# Stepper_Motor_Driver.net
KiCad netlist of a schematic drawn in Altium Designer
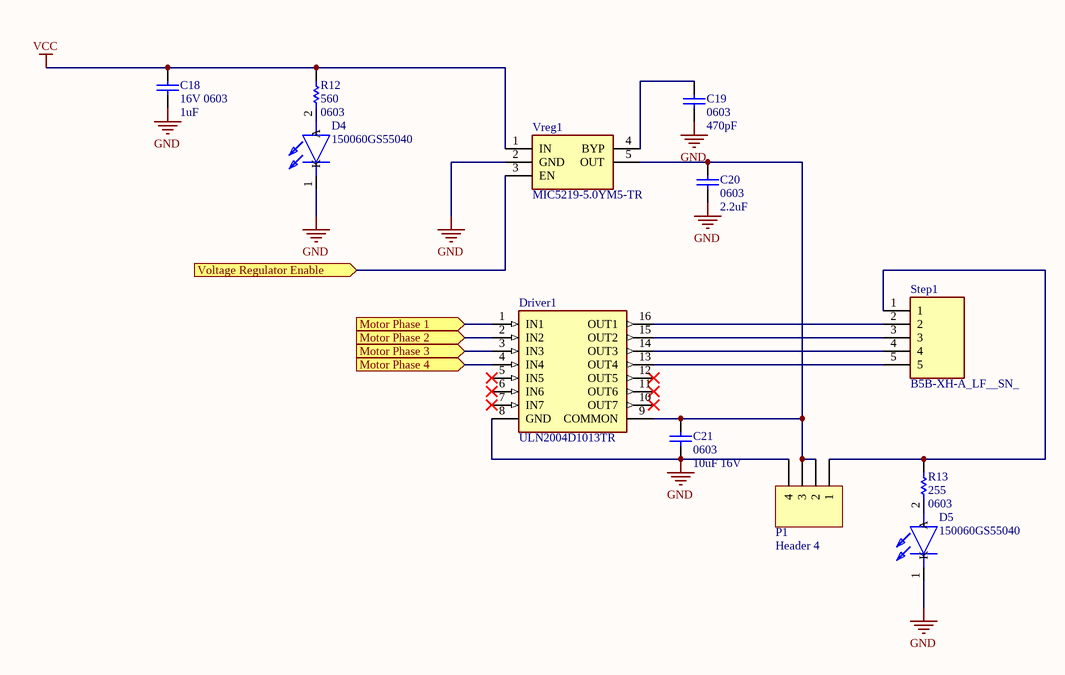
[diagram p0: Stepper Motor Driver.SchDoc]

(export (version "E")
  (design (tool "Eeschema 10.0.6"))
  (components
    (comp (ref "C18")
      (value "16V 0603")
      (footprint "SMD-0603C")
      (description "Capacitor")
      (fields (field (name "ALTIUM_VALUE") "1uF") (field (name "PUBLISHER") "Altium Limited"))
      (libsource (lib "Miscellaneous Devices") (part "Cap"))
    )
    (comp (ref "C19")
      (value "0603")
      (footprint "SMD-0603C")
      (description "Capacitor")
      (fields (field (name "ALTIUM_VALUE") "470pF") (field (name "PUBLISHER") "Altium Limited"))
      (libsource (lib "Miscellaneous Devices") (part "Cap"))
    )
    (comp (ref "C20")
      (value "0603")
      (footprint "SMD-0603C")
      (description "Capacitor")
      (fields (field (name "ALTIUM_VALUE") "2.2uF") (field (name "PUBLISHER") "Altium Limited"))
      (libsource (lib "Miscellaneous Devices") (part "Cap"))
    )
    (comp (ref "C21")
      (value "0603")
      (footprint "SMD-0603C")
      (description "Capacitor")
      (fields (field (name "ALTIUM_VALUE") "10uF 16V") (field (name "PUBLISHER") "Altium Limited"))
      (libsource (lib "Miscellaneous Devices") (part "Cap"))
    )
    (comp (ref "D4")
      (value "150060GS55040")
      (footprint "SamacSys:LEDC1608X50N")
      (description "LED")
      (fields
        (field (name "MOUSER PART NUMBER") "710-150060GS55040")
        (field (name "RS PART NUMBER") "1766068P")
      )
      (libsource (lib "*") (part "150060GS55040"))
    )
    (comp (ref "D5")
      (value "150060GS55040")
      (footprint "SamacSys:LEDC1608X50N")
      (description "LED")
      (fields
        (field (name "MOUSER PART NUMBER") "710-150060GS55040")
        (field (name "RS PART NUMBER") "1766068P")
      )
      (libsource (lib "*") (part "150060GS55040"))
    )
    (comp (ref "Driver1")
      (value "ULN2004D1013TR")
      (footprint "SamacSys:SOIC127P600X175-16N")
      (description "Integrated Circuit")
      (fields
        (field (name "MOUSER PART NUMBER") "511-ULN2004D1013TR")
        (field (name "RS PART NUMBER") "6868161P")
      )
      (libsource (lib "*") (part "ULN2004D1013TR"))
    )
    (comp (ref "P1")
      (value "Header 4")
      (footprint "HDR1X4")
      (description "Header, 4-Pin")
      (fields (field (name "PUBLISHER") "Altium Limited"))
      (libsource (lib "Miscellaneous Connectors") (part "Header 4"))
    )
    (comp (ref "R12")
      (value "560")
      (footprint "SMD-0603-RES")
      (description "Resistor")
      (fields (field (name "ALTIUM_VALUE") "0603") (field (name "PUBLISHER") "Altium Limited"))
      (libsource (lib "Miscellaneous Devices") (part "Res1"))
    )
    (comp (ref "R13")
      (value "255")
      (footprint "SMD-0603-RES")
      (description "Resistor")
      (fields (field (name "ALTIUM_VALUE") "0603") (field (name "PUBLISHER") "Altium Limited"))
      (libsource (lib "Miscellaneous Devices") (part "Res1"))
    )
    (comp (ref "Step1")
      (value "B5B-XH-A_LF__SN_")
      (footprint "SamacSys:SHDR5W64P0X250_1X5_1490X575X700P")
      (description "28BYJ-48 Stepper Motor")
      (fields
        (field (name "MANUFACTURER_PART_NUMBER") "B5B-XH-A(LF)(SN)")
        (field (name "RS PART NUMBER") "8201560P")
      )
      (libsource (lib "*") (part "B5B-XH-A_LF__SN_"))
    )
    (comp (ref "Vreg1")
      (value "MIC5219-5.0YM5-TR")
      (footprint "SamacSys:SOT95P280X145-5N")
      (description "Integrated Circuit")
      (fields
        (field (name "MOUSER PART NUMBER") "998-MIC5219-5.0YM5TR")
        (field (name "RS PART NUMBER") "9101755P")
      )
      (libsource (lib "*") (part "MIC5219-5.0YM5-TR"))
    )
  )
  (nets
    (net (code "1") (name "/Motor Phase 1") (class "Default")
      (node (ref "Driver1") (pin "1") (pinfunction "IN1_1") (pintype "input"))
    )
    (net (code "2") (name "/Motor Phase 2") (class "Default")
      (node (ref "Driver1") (pin "2") (pinfunction "IN2_2") (pintype "input"))
    )
    (net (code "3") (name "/Motor Phase 3") (class "Default")
      (node (ref "Driver1") (pin "3") (pinfunction "IN3_3") (pintype "input"))
    )
    (net (code "4") (name "/Motor Phase 4") (class "Default")
      (node (ref "Driver1") (pin "4") (pinfunction "IN4_4") (pintype "input"))
    )
    (net (code "5") (name "/Voltage Regulator Enable") (class "Default")
      (node (ref "Vreg1") (pin "3") (pinfunction "EN_3") (pintype "passive"))
    )
    (net (code "6") (name "GND") (class "Default")
      (node (ref "C18") (pin "1") (pinfunction "1_1") (pintype "passive"))
      (node (ref "C19") (pin "1") (pinfunction "1_1") (pintype "passive"))
      (node (ref "C20") (pin "1") (pinfunction "1_1") (pintype "passive"))
      (node (ref "C21") (pin "1") (pinfunction "1_1") (pintype "passive"))
      (node (ref "D4") (pin "1") (pinfunction "K_1") (pintype "passive"))
      (node (ref "D5") (pin "1") (pinfunction "K_1") (pintype "passive"))
      (node (ref "Driver1") (pin "8") (pinfunction "GND_8") (pintype "power_in"))
      (node (ref "P1") (pin "4") (pinfunction "4_4") (pintype "passive"))
      (node (ref "Vreg1") (pin "2") (pinfunction "GND_2") (pintype "passive"))
    )
    (net (code "7") (name "Net-(D4-A)") (class "Default")
      (node (ref "D4") (pin "2") (pinfunction "A_2") (pintype "passive"))
      (node (ref "R12") (pin "2") (pinfunction "2_2") (pintype "passive"))
    )
    (net (code "8") (name "Net-(D5-A)") (class "Default")
      (node (ref "D5") (pin "2") (pinfunction "A_2") (pintype "passive"))
      (node (ref "R13") (pin "2") (pinfunction "2_2") (pintype "passive"))
    )
    (net (code "9") (name "Net-(Driver1-COMMON)") (class "Default")
      (node (ref "C20") (pin "2") (pinfunction "2_2") (pintype "passive"))
      (node (ref "C21") (pin "2") (pinfunction "2_2") (pintype "passive"))
      (node (ref "Driver1") (pin "9") (pinfunction "COMMON_9") (pintype "passive"))
      (node (ref "P1") (pin "2") (pinfunction "2_2") (pintype "passive"))
      (node (ref "P1") (pin "3") (pinfunction "3_3") (pintype "passive"))
      (node (ref "Vreg1") (pin "5") (pinfunction "OUT_5") (pintype "passive"))
    )
    (net (code "10") (name "Net-(Driver1-OUT1)") (class "Default")
      (node (ref "Driver1") (pin "16") (pinfunction "OUT1_16") (pintype "output"))
      (node (ref "Step1") (pin "2") (pinfunction "2_2") (pintype "passive"))
    )
    (net (code "11") (name "Net-(Driver1-OUT2)") (class "Default")
      (node (ref "Driver1") (pin "15") (pinfunction "OUT2_15") (pintype "output"))
      (node (ref "Step1") (pin "3") (pinfunction "3_3") (pintype "passive"))
    )
    (net (code "12") (name "Net-(Driver1-OUT3)") (class "Default")
      (node (ref "Driver1") (pin "14") (pinfunction "OUT3_14") (pintype "output"))
      (node (ref "Step1") (pin "4") (pinfunction "4_4") (pintype "passive"))
    )
    (net (code "13") (name "Net-(Driver1-OUT4)") (class "Default")
      (node (ref "Driver1") (pin "13") (pinfunction "OUT4_13") (pintype "output"))
      (node (ref "Step1") (pin "5") (pinfunction "5_5") (pintype "passive"))
    )
    (net (code "14") (name "Net-(P1-Pad1)") (class "Default")
      (node (ref "P1") (pin "1") (pinfunction "1_1") (pintype "passive"))
      (node (ref "R13") (pin "1") (pinfunction "1_1") (pintype "passive"))
      (node (ref "Step1") (pin "1") (pinfunction "1_1") (pintype "passive"))
    )
    (net (code "15") (name "Net-(Vreg1-BYP)") (class "Default")
      (node (ref "C19") (pin "2") (pinfunction "2_2") (pintype "passive"))
      (node (ref "Vreg1") (pin "4") (pinfunction "BYP_4") (pintype "passive"))
    )
    (net (code "16") (name "VCC") (class "Default")
      (node (ref "C18") (pin "2") (pinfunction "2_2") (pintype "passive"))
      (node (ref "R12") (pin "1") (pinfunction "1_1") (pintype "passive"))
      (node (ref "Vreg1") (pin "1") (pinfunction "IN_1") (pintype "passive"))
    )
    (net (code "17") (name "unconnected-(Driver1-IN5-Pad5)") (class "Default")
      (node (ref "Driver1") (pin "5") (pinfunction "IN5_5") (pintype "input+no_connect"))
    )
    (net (code "18") (name "unconnected-(Driver1-IN6-Pad6)") (class "Default")
      (node (ref "Driver1") (pin "6") (pinfunction "IN6_6") (pintype "input+no_connect"))
    )
    (net (code "19") (name "unconnected-(Driver1-IN7-Pad7)") (class "Default")
      (node (ref "Driver1") (pin "7") (pinfunction "IN7_7") (pintype "input+no_connect"))
    )
    (net (code "20") (name "unconnected-(Driver1-OUT5-Pad12)") (class "Default")
      (node (ref "Driver1") (pin "12") (pinfunction "OUT5_12") (pintype "output+no_connect"))
    )
    (net (code "21") (name "unconnected-(Driver1-OUT6-Pad11)") (class "Default")
      (node (ref "Driver1") (pin "11") (pinfunction "OUT6_11") (pintype "output+no_connect"))
    )
    (net (code "22") (name "unconnected-(Driver1-OUT7-Pad10)") (class "Default")
      (node (ref "Driver1") (pin "10") (pinfunction "OUT7_10") (pintype "output+no_connect"))
    )
  )
)
